# mainSchematic.net
KiCad netlist of a schematic drawn in Altium Designer
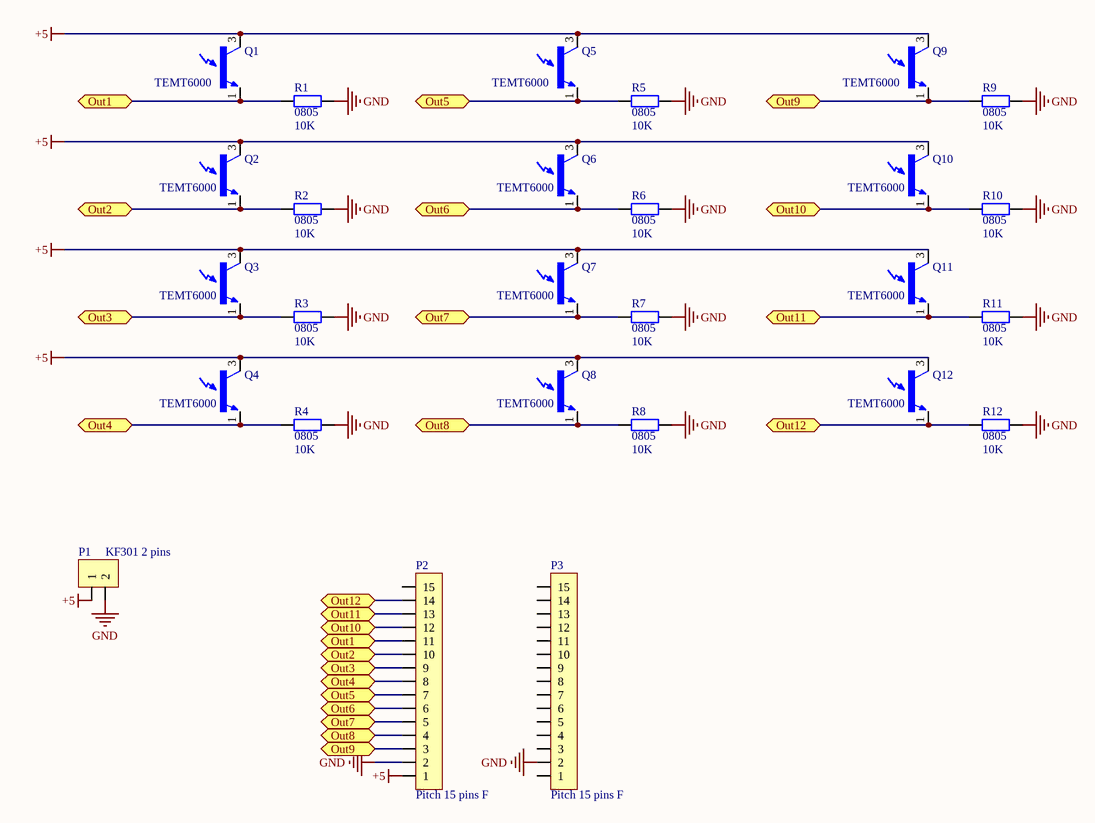
[diagram p0: mainSchematic.SchDoc]

(export (version "E")
  (design (tool "Eeschema 10.0.6"))
  (components
    (comp (ref "P1")
      (value "KF301 2 pins")
      (footprint "Kf301 2 PINS")
      (description "KF301 16A")
      (libsource (lib "LibraryBrenoQueiroz") (part "KF301 2 pins"))
    )
    (comp (ref "P2")
      (value "Pitch 15 pins F")
      (footprint "Pitch female 15 pins")
      (libsource (lib "LibraryBrenoQueiroz") (part "Pitch 15 pins F"))
    )
    (comp (ref "P3")
      (value "Pitch 15 pins F")
      (footprint "Pitch female 15 pins")
      (libsource (lib "LibraryBrenoQueiroz") (part "Pitch 15 pins F"))
    )
    (comp (ref "Q1")
      (value "TEMT6000")
      (footprint "TEMT6000")
      (description "TEMT6000 LDR SMD")
      (libsource (lib "LibraryBrenoQueiroz") (part "TEMT6000"))
    )
    (comp (ref "Q2")
      (value "TEMT6000")
      (footprint "TEMT6000")
      (description "TEMT6000 LDR SMD")
      (libsource (lib "LibraryBrenoQueiroz") (part "TEMT6000"))
    )
    (comp (ref "Q3")
      (value "TEMT6000")
      (footprint "TEMT6000")
      (description "TEMT6000 LDR SMD")
      (libsource (lib "LibraryBrenoQueiroz") (part "TEMT6000"))
    )
    (comp (ref "Q4")
      (value "TEMT6000")
      (footprint "TEMT6000")
      (description "TEMT6000 LDR SMD")
      (libsource (lib "LibraryBrenoQueiroz") (part "TEMT6000"))
    )
    (comp (ref "Q5")
      (value "TEMT6000")
      (footprint "TEMT6000")
      (description "TEMT6000 LDR SMD")
      (libsource (lib "LibraryBrenoQueiroz") (part "TEMT6000"))
    )
    (comp (ref "Q6")
      (value "TEMT6000")
      (footprint "TEMT6000")
      (description "TEMT6000 LDR SMD")
      (libsource (lib "LibraryBrenoQueiroz") (part "TEMT6000"))
    )
    (comp (ref "Q7")
      (value "TEMT6000")
      (footprint "TEMT6000")
      (description "TEMT6000 LDR SMD")
      (libsource (lib "LibraryBrenoQueiroz") (part "TEMT6000"))
    )
    (comp (ref "Q8")
      (value "TEMT6000")
      (footprint "TEMT6000")
      (description "TEMT6000 LDR SMD")
      (libsource (lib "LibraryBrenoQueiroz") (part "TEMT6000"))
    )
    (comp (ref "Q9")
      (value "TEMT6000")
      (footprint "TEMT6000")
      (description "TEMT6000 LDR SMD")
      (libsource (lib "LibraryBrenoQueiroz") (part "TEMT6000"))
    )
    (comp (ref "Q10")
      (value "TEMT6000")
      (footprint "TEMT6000")
      (description "TEMT6000 LDR SMD")
      (libsource (lib "LibraryBrenoQueiroz") (part "TEMT6000"))
    )
    (comp (ref "Q11")
      (value "TEMT6000")
      (footprint "TEMT6000")
      (description "TEMT6000 LDR SMD")
      (libsource (lib "LibraryBrenoQueiroz") (part "TEMT6000"))
    )
    (comp (ref "Q12")
      (value "TEMT6000")
      (footprint "TEMT6000")
      (description "TEMT6000 LDR SMD")
      (libsource (lib "LibraryBrenoQueiroz") (part "TEMT6000"))
    )
    (comp (ref "R1")
      (value "0805")
      (footprint "Resistor SMD 0805")
      (description "Resistor SMD 0805")
      (fields (field (name "ALTIUM_VALUE") "10K"))
      (libsource (lib "LibraryBrenoQueiroz") (part "Resistor SMD 0805"))
    )
    (comp (ref "R2")
      (value "0805")
      (footprint "Resistor SMD 0805")
      (description "Resistor SMD 0805")
      (fields (field (name "ALTIUM_VALUE") "10K"))
      (libsource (lib "LibraryBrenoQueiroz") (part "Resistor SMD 0805"))
    )
    (comp (ref "R3")
      (value "0805")
      (footprint "Resistor SMD 0805")
      (description "Resistor SMD 0805")
      (fields (field (name "ALTIUM_VALUE") "10K"))
      (libsource (lib "LibraryBrenoQueiroz") (part "Resistor SMD 0805"))
    )
    (comp (ref "R4")
      (value "0805")
      (footprint "Resistor SMD 0805")
      (description "Resistor SMD 0805")
      (fields (field (name "ALTIUM_VALUE") "10K"))
      (libsource (lib "LibraryBrenoQueiroz") (part "Resistor SMD 0805"))
    )
    (comp (ref "R5")
      (value "0805")
      (footprint "Resistor SMD 0805")
      (description "Resistor SMD 0805")
      (fields (field (name "ALTIUM_VALUE") "10K"))
      (libsource (lib "LibraryBrenoQueiroz") (part "Resistor SMD 0805"))
    )
    (comp (ref "R6")
      (value "0805")
      (footprint "Resistor SMD 0805")
      (description "Resistor SMD 0805")
      (fields (field (name "ALTIUM_VALUE") "10K"))
      (libsource (lib "LibraryBrenoQueiroz") (part "Resistor SMD 0805"))
    )
    (comp (ref "R7")
      (value "0805")
      (footprint "Resistor SMD 0805")
      (description "Resistor SMD 0805")
      (fields (field (name "ALTIUM_VALUE") "10K"))
      (libsource (lib "LibraryBrenoQueiroz") (part "Resistor SMD 0805"))
    )
    (comp (ref "R8")
      (value "0805")
      (footprint "Resistor SMD 0805")
      (description "Resistor SMD 0805")
      (fields (field (name "ALTIUM_VALUE") "10K"))
      (libsource (lib "LibraryBrenoQueiroz") (part "Resistor SMD 0805"))
    )
    (comp (ref "R9")
      (value "0805")
      (footprint "Resistor SMD 0805")
      (description "Resistor SMD 0805")
      (fields (field (name "ALTIUM_VALUE") "10K"))
      (libsource (lib "LibraryBrenoQueiroz") (part "Resistor SMD 0805"))
    )
    (comp (ref "R10")
      (value "0805")
      (footprint "Resistor SMD 0805")
      (description "Resistor SMD 0805")
      (fields (field (name "ALTIUM_VALUE") "10K"))
      (libsource (lib "LibraryBrenoQueiroz") (part "Resistor SMD 0805"))
    )
    (comp (ref "R11")
      (value "0805")
      (footprint "Resistor SMD 0805")
      (description "Resistor SMD 0805")
      (fields (field (name "ALTIUM_VALUE") "10K"))
      (libsource (lib "LibraryBrenoQueiroz") (part "Resistor SMD 0805"))
    )
    (comp (ref "R12")
      (value "0805")
      (footprint "Resistor SMD 0805")
      (description "Resistor SMD 0805")
      (fields (field (name "ALTIUM_VALUE") "10K"))
      (libsource (lib "LibraryBrenoQueiroz") (part "Resistor SMD 0805"))
    )
  )
  (nets
    (net (code "1") (name "+5") (class "Default")
      (node (ref "P1") (pin "1") (pinfunction "1_1") (pintype "passive"))
      (node (ref "P2") (pin "1") (pinfunction "1_1") (pintype "passive"))
      (node (ref "Q1") (pin "3") (pinfunction "3_3") (pintype "passive"))
      (node (ref "Q10") (pin "3") (pinfunction "3_3") (pintype "passive"))
      (node (ref "Q11") (pin "3") (pinfunction "3_3") (pintype "passive"))
      (node (ref "Q12") (pin "3") (pinfunction "3_3") (pintype "passive"))
      (node (ref "Q2") (pin "3") (pinfunction "3_3") (pintype "passive"))
      (node (ref "Q3") (pin "3") (pinfunction "3_3") (pintype "passive"))
      (node (ref "Q4") (pin "3") (pinfunction "3_3") (pintype "passive"))
      (node (ref "Q5") (pin "3") (pinfunction "3_3") (pintype "passive"))
      (node (ref "Q6") (pin "3") (pinfunction "3_3") (pintype "passive"))
      (node (ref "Q7") (pin "3") (pinfunction "3_3") (pintype "passive"))
      (node (ref "Q8") (pin "3") (pinfunction "3_3") (pintype "passive"))
      (node (ref "Q9") (pin "3") (pinfunction "3_3") (pintype "passive"))
    )
    (net (code "2") (name "/Out1") (class "Default")
      (node (ref "P2") (pin "11") (pinfunction "11_11") (pintype "passive"))
      (node (ref "Q1") (pin "1") (pinfunction "1_1") (pintype "passive"))
      (node (ref "R1") (pin "1") (pinfunction "1_1") (pintype "passive"))
    )
    (net (code "3") (name "/Out2") (class "Default")
      (node (ref "P2") (pin "10") (pinfunction "10_10") (pintype "passive"))
      (node (ref "Q2") (pin "1") (pinfunction "1_1") (pintype "passive"))
      (node (ref "R2") (pin "1") (pinfunction "1_1") (pintype "passive"))
    )
    (net (code "4") (name "/Out3") (class "Default")
      (node (ref "P2") (pin "9") (pinfunction "9_9") (pintype "passive"))
      (node (ref "Q3") (pin "1") (pinfunction "1_1") (pintype "passive"))
      (node (ref "R3") (pin "1") (pinfunction "1_1") (pintype "passive"))
    )
    (net (code "5") (name "/Out4") (class "Default")
      (node (ref "P2") (pin "8") (pinfunction "8_8") (pintype "passive"))
      (node (ref "Q4") (pin "1") (pinfunction "1_1") (pintype "passive"))
      (node (ref "R4") (pin "1") (pinfunction "1_1") (pintype "passive"))
    )
    (net (code "6") (name "/Out5") (class "Default")
      (node (ref "P2") (pin "7") (pinfunction "7_7") (pintype "passive"))
      (node (ref "Q5") (pin "1") (pinfunction "1_1") (pintype "passive"))
      (node (ref "R5") (pin "1") (pinfunction "1_1") (pintype "passive"))
    )
    (net (code "7") (name "/Out6") (class "Default")
      (node (ref "P2") (pin "6") (pinfunction "6_6") (pintype "passive"))
      (node (ref "Q6") (pin "1") (pinfunction "1_1") (pintype "passive"))
      (node (ref "R6") (pin "1") (pinfunction "1_1") (pintype "passive"))
    )
    (net (code "8") (name "/Out7") (class "Default")
      (node (ref "P2") (pin "5") (pinfunction "5_5") (pintype "passive"))
      (node (ref "Q7") (pin "1") (pinfunction "1_1") (pintype "passive"))
      (node (ref "R7") (pin "1") (pinfunction "1_1") (pintype "passive"))
    )
    (net (code "9") (name "/Out8") (class "Default")
      (node (ref "P2") (pin "4") (pinfunction "4_4") (pintype "passive"))
      (node (ref "Q8") (pin "1") (pinfunction "1_1") (pintype "passive"))
      (node (ref "R8") (pin "1") (pinfunction "1_1") (pintype "passive"))
    )
    (net (code "10") (name "/Out9") (class "Default")
      (node (ref "P2") (pin "3") (pinfunction "3_3") (pintype "passive"))
      (node (ref "Q9") (pin "1") (pinfunction "1_1") (pintype "passive"))
      (node (ref "R9") (pin "1") (pinfunction "1_1") (pintype "passive"))
    )
    (net (code "11") (name "/Out10") (class "Default")
      (node (ref "P2") (pin "12") (pinfunction "12_12") (pintype "passive"))
      (node (ref "Q10") (pin "1") (pinfunction "1_1") (pintype "passive"))
      (node (ref "R10") (pin "1") (pinfunction "1_1") (pintype "passive"))
    )
    (net (code "12") (name "/Out11") (class "Default")
      (node (ref "P2") (pin "13") (pinfunction "13_13") (pintype "passive"))
      (node (ref "Q11") (pin "1") (pinfunction "1_1") (pintype "passive"))
      (node (ref "R11") (pin "1") (pinfunction "1_1") (pintype "passive"))
    )
    (net (code "13") (name "/Out12") (class "Default")
      (node (ref "P2") (pin "14") (pinfunction "14_14") (pintype "passive"))
      (node (ref "Q12") (pin "1") (pinfunction "1_1") (pintype "passive"))
      (node (ref "R12") (pin "1") (pinfunction "1_1") (pintype "passive"))
    )
    (net (code "14") (name "GND") (class "Default")
      (node (ref "P1") (pin "2") (pinfunction "2_2") (pintype "passive"))
      (node (ref "P2") (pin "2") (pinfunction "2_2") (pintype "passive"))
      (node (ref "P3") (pin "2") (pinfunction "2_2") (pintype "passive"))
      (node (ref "R1") (pin "2") (pinfunction "2_2") (pintype "passive"))
      (node (ref "R10") (pin "2") (pinfunction "2_2") (pintype "passive"))
      (node (ref "R11") (pin "2") (pinfunction "2_2") (pintype "passive"))
      (node (ref "R12") (pin "2") (pinfunction "2_2") (pintype "passive"))
      (node (ref "R2") (pin "2") (pinfunction "2_2") (pintype "passive"))
      (node (ref "R3") (pin "2") (pinfunction "2_2") (pintype "passive"))
      (node (ref "R4") (pin "2") (pinfunction "2_2") (pintype "passive"))
      (node (ref "R5") (pin "2") (pinfunction "2_2") (pintype "passive"))
      (node (ref "R6") (pin "2") (pinfunction "2_2") (pintype "passive"))
      (node (ref "R7") (pin "2") (pinfunction "2_2") (pintype "passive"))
      (node (ref "R8") (pin "2") (pinfunction "2_2") (pintype "passive"))
      (node (ref "R9") (pin "2") (pinfunction "2_2") (pintype "passive"))
    )
    (net (code "15") (name "unconnected-(P2-Pad15)") (class "Default")
      (node (ref "P2") (pin "15") (pinfunction "15_15") (pintype "passive"))
    )
    (net (code "16") (name "unconnected-(P3-Pad1)") (class "Default")
      (node (ref "P3") (pin "1") (pinfunction "1_1") (pintype "passive"))
    )
    (net (code "17") (name "unconnected-(P3-Pad3)") (class "Default")
      (node (ref "P3") (pin "3") (pinfunction "3_3") (pintype "passive"))
    )
    (net (code "18") (name "unconnected-(P3-Pad4)") (class "Default")
      (node (ref "P3") (pin "4") (pinfunction "4_4") (pintype "passive"))
    )
    (net (code "19") (name "unconnected-(P3-Pad5)") (class "Default")
      (node (ref "P3") (pin "5") (pinfunction "5_5") (pintype "passive"))
    )
    (net (code "20") (name "unconnected-(P3-Pad6)") (class "Default")
      (node (ref "P3") (pin "6") (pinfunction "6_6") (pintype "passive"))
    )
    (net (code "21") (name "unconnected-(P3-Pad7)") (class "Default")
      (node (ref "P3") (pin "7") (pinfunction "7_7") (pintype "passive"))
    )
    (net (code "22") (name "unconnected-(P3-Pad8)") (class "Default")
      (node (ref "P3") (pin "8") (pinfunction "8_8") (pintype "passive"))
    )
    (net (code "23") (name "unconnected-(P3-Pad9)") (class "Default")
      (node (ref "P3") (pin "9") (pinfunction "9_9") (pintype "passive"))
    )
    (net (code "24") (name "unconnected-(P3-Pad10)") (class "Default")
      (node (ref "P3") (pin "10") (pinfunction "10_10") (pintype "passive"))
    )
    (net (code "25") (name "unconnected-(P3-Pad11)") (class "Default")
      (node (ref "P3") (pin "11") (pinfunction "11_11") (pintype "passive"))
    )
    (net (code "26") (name "unconnected-(P3-Pad12)") (class "Default")
      (node (ref "P3") (pin "12") (pinfunction "12_12") (pintype "passive"))
    )
    (net (code "27") (name "unconnected-(P3-Pad13)") (class "Default")
      (node (ref "P3") (pin "13") (pinfunction "13_13") (pintype "passive"))
    )
    (net (code "28") (name "unconnected-(P3-Pad14)") (class "Default")
      (node (ref "P3") (pin "14") (pinfunction "14_14") (pintype "passive"))
    )
    (net (code "29") (name "unconnected-(P3-Pad15)") (class "Default")
      (node (ref "P3") (pin "15") (pinfunction "15_15") (pintype "passive"))
    )
  )
)
